# Main_4.net
KiCad netlist of a schematic drawn in Altium Designer
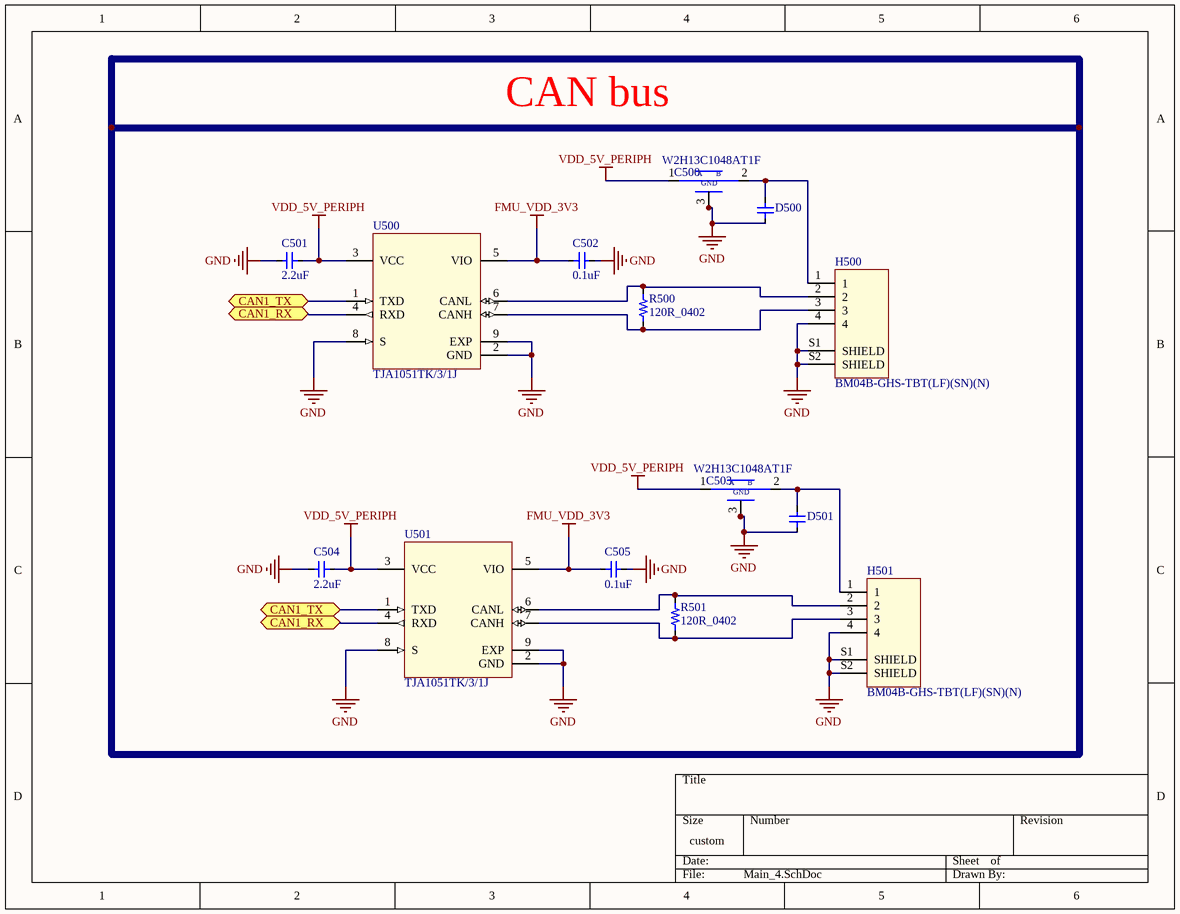
[diagram p0: Main_4.SchDoc]

(export (version "E")
  (design (tool "Eeschema 10.0.6"))
  (components
    (comp (ref "C500")
      (value "W2H13C1048AT1F")
      (footprint "W2H13C1048AT1F")
      (description "Feed Through Capacitors 25V 0.1uF X7R")
      (libsource (lib "UAV_mainboard") (part "W2H13C1048AT1F"))
    )
    (comp (ref "C501")
      (value "2.2uF")
      (footprint "C0603")
      (description "2.2 µF ±10% 10V Ceramic Capacitor X5R 0603 (1608 Metric)")
      (libsource (lib "UAV_mainboard") (part "CC0603KPX5R6BB225"))
    )
    (comp (ref "C502")
      (value "0.1uF")
      (footprint "C0603")
      (description "CAP CER 0.1UF 25V X7R 0603")
      (libsource (lib "UAV_mainboard") (part "CC0603KRX7R8BB104"))
    )
    (comp (ref "C503")
      (value "W2H13C1048AT1F")
      (footprint "W2H13C1048AT1F")
      (description "Feed Through Capacitors 25V 0.1uF X7R")
      (libsource (lib "UAV_mainboard") (part "W2H13C1048AT1F"))
    )
    (comp (ref "C504")
      (value "2.2uF")
      (footprint "C0603")
      (description "2.2 µF ±10% 10V Ceramic Capacitor X5R 0603 (1608 Metric)")
      (libsource (lib "UAV_mainboard") (part "CC0603KPX5R6BB225"))
    )
    (comp (ref "C505")
      (value "0.1uF")
      (footprint "C0603")
      (description "CAP CER 0.1UF 25V X7R 0603")
      (libsource (lib "UAV_mainboard") (part "CC0603KRX7R8BB104"))
    )
    (comp (ref "D500")
      (value "PESD0402-140")
      (footprint "PESD0402-140")
      (description "40V Clamp - Ipp Tvs Diode Surface Mount 0402")
      (libsource (lib "UAV_mainboard") (part "PESD0402-140"))
    )
    (comp (ref "D501")
      (value "PESD0402-140")
      (footprint "PESD0402-140")
      (description "40V Clamp - Ipp Tvs Diode Surface Mount 0402")
      (libsource (lib "UAV_mainboard") (part "PESD0402-140"))
    )
    (comp (ref "H500")
      (value "BM04B-GHS-TBT(LF)(SN)(N)")
      (footprint "BM04B-GHS-TBT(LF)(SN)(N)")
      (description "Connector Header Surface Mount 4 position 0.049\" (1.25mm)")
      (libsource (lib "UAV_mainboard") (part "BM04B-GHS-TBT(LF)(SN)(N)"))
    )
    (comp (ref "H501")
      (value "BM04B-GHS-TBT(LF)(SN)(N)")
      (footprint "BM04B-GHS-TBT(LF)(SN)(N)")
      (description "Connector Header Surface Mount 4 position 0.049\" (1.25mm)")
      (libsource (lib "UAV_mainboard") (part "BM04B-GHS-TBT(LF)(SN)(N)"))
    )
    (comp (ref "R500")
      (value "120R_0402")
      (footprint "R0402")
      (description "120 Ohms ±1% 0.063W, 1/16W Chip Resistor 0402 (1005 Metric) Moisture Resistant Thick Film")
      (libsource (lib "UAV_mainboard") (part "RC0402FR-07120RL"))
    )
    (comp (ref "R501")
      (value "120R_0402")
      (footprint "R0402")
      (description "120 Ohms ±1% 0.063W, 1/16W Chip Resistor 0402 (1005 Metric) Moisture Resistant Thick Film")
      (libsource (lib "UAV_mainboard") (part "RC0402FR-07120RL"))
    )
    (comp (ref "U500")
      (value "TJA1051TK/3/1J")
      (footprint "8HVSON")
      (description "IC TRANSCEIVER HALF 1/1 8HVSON")
      (libsource (lib "UAV_mainboard") (part "TJA1051TK/3/1J"))
    )
    (comp (ref "U501")
      (value "TJA1051TK/3/1J")
      (footprint "8HVSON")
      (description "IC TRANSCEIVER HALF 1/1 8HVSON")
      (libsource (lib "UAV_mainboard") (part "TJA1051TK/3/1J"))
    )
  )
  (nets
    (net (code "1") (name "/CAN1_RX") (class "Default")
      (node (ref "U500") (pin "4") (pinfunction "RXD_4") (pintype "output"))
      (node (ref "U501") (pin "4") (pinfunction "RXD_4") (pintype "output"))
    )
    (net (code "2") (name "/CAN1_TX") (class "Default")
      (node (ref "U500") (pin "1") (pinfunction "TXD_1") (pintype "input"))
      (node (ref "U501") (pin "1") (pinfunction "TXD_1") (pintype "input"))
    )
    (net (code "3") (name "FMU_VDD_3V3") (class "Default")
      (node (ref "C502") (pin "1") (pinfunction "1_1") (pintype "passive"))
      (node (ref "C505") (pin "1") (pinfunction "1_1") (pintype "passive"))
      (node (ref "U500") (pin "5") (pinfunction "VIO_5") (pintype "power_in"))
      (node (ref "U501") (pin "5") (pinfunction "VIO_5") (pintype "power_in"))
    )
    (net (code "4") (name "GND") (class "Default")
      (node (ref "C500") (pin "3") (pintype "passive"))
      (node (ref "C500") (pin "4") (pinfunction "4_4") (pintype "passive"))
      (node (ref "C501") (pin "2") (pinfunction "2_2") (pintype "passive"))
      (node (ref "C502") (pin "2") (pinfunction "2_2") (pintype "passive"))
      (node (ref "C503") (pin "3") (pintype "passive"))
      (node (ref "C503") (pin "4") (pinfunction "4_4") (pintype "passive"))
      (node (ref "C504") (pin "2") (pinfunction "2_2") (pintype "passive"))
      (node (ref "C505") (pin "2") (pinfunction "2_2") (pintype "passive"))
      (node (ref "D500") (pin "1") (pinfunction "1_1") (pintype "passive"))
      (node (ref "D501") (pin "1") (pinfunction "1_1") (pintype "passive"))
      (node (ref "H500") (pin "4") (pinfunction "4_4") (pintype "passive"))
      (node (ref "H500") (pin "S1") (pinfunction "SHIELD_S1") (pintype "passive"))
      (node (ref "H500") (pin "S2") (pinfunction "SHIELD_S2") (pintype "passive"))
      (node (ref "H501") (pin "4") (pinfunction "4_4") (pintype "passive"))
      (node (ref "H501") (pin "S1") (pinfunction "SHIELD_S1") (pintype "passive"))
      (node (ref "H501") (pin "S2") (pinfunction "SHIELD_S2") (pintype "passive"))
      (node (ref "U500") (pin "2") (pinfunction "GND_2") (pintype "power_in"))
      (node (ref "U500") (pin "8") (pinfunction "S_8") (pintype "input"))
      (node (ref "U500") (pin "9") (pinfunction "EXP_9") (pintype "power_in"))
      (node (ref "U501") (pin "2") (pinfunction "GND_2") (pintype "power_in"))
      (node (ref "U501") (pin "8") (pinfunction "S_8") (pintype "input"))
      (node (ref "U501") (pin "9") (pinfunction "EXP_9") (pintype "power_in"))
    )
    (net (code "5") (name "Net-(C500-Pad2)") (class "Default")
      (node (ref "C500") (pin "2") (pintype "passive"))
      (node (ref "D500") (pin "2") (pinfunction "2_2") (pintype "passive"))
      (node (ref "H500") (pin "1") (pinfunction "1_1") (pintype "passive"))
    )
    (net (code "6") (name "Net-(C503-Pad2)") (class "Default")
      (node (ref "C503") (pin "2") (pintype "passive"))
      (node (ref "D501") (pin "2") (pinfunction "2_2") (pintype "passive"))
      (node (ref "H501") (pin "1") (pinfunction "1_1") (pintype "passive"))
    )
    (net (code "7") (name "Net-(U500-CANH)") (class "Default")
      (node (ref "H500") (pin "3") (pinfunction "3_3") (pintype "passive"))
      (node (ref "R500") (pin "1") (pinfunction "1_1") (pintype "passive"))
      (node (ref "U500") (pin "7") (pinfunction "CANH_7") (pintype "bidirectional"))
    )
    (net (code "8") (name "Net-(U500-CANL)") (class "Default")
      (node (ref "H500") (pin "2") (pinfunction "2_2") (pintype "passive"))
      (node (ref "R500") (pin "2") (pinfunction "2_2") (pintype "passive"))
      (node (ref "U500") (pin "6") (pinfunction "CANL_6") (pintype "bidirectional"))
    )
    (net (code "9") (name "Net-(U501-CANH)") (class "Default")
      (node (ref "H501") (pin "3") (pinfunction "3_3") (pintype "passive"))
      (node (ref "R501") (pin "1") (pinfunction "1_1") (pintype "passive"))
      (node (ref "U501") (pin "7") (pinfunction "CANH_7") (pintype "bidirectional"))
    )
    (net (code "10") (name "Net-(U501-CANL)") (class "Default")
      (node (ref "H501") (pin "2") (pinfunction "2_2") (pintype "passive"))
      (node (ref "R501") (pin "2") (pinfunction "2_2") (pintype "passive"))
      (node (ref "U501") (pin "6") (pinfunction "CANL_6") (pintype "bidirectional"))
    )
    (net (code "11") (name "VDD_5V_PERIPH") (class "Default")
      (node (ref "C500") (pin "1") (pintype "passive"))
      (node (ref "C501") (pin "1") (pinfunction "1_1") (pintype "passive"))
      (node (ref "C503") (pin "1") (pintype "passive"))
      (node (ref "C504") (pin "1") (pinfunction "1_1") (pintype "passive"))
      (node (ref "U500") (pin "3") (pinfunction "VCC_3") (pintype "power_in"))
      (node (ref "U501") (pin "3") (pinfunction "VCC_3") (pintype "power_in"))
    )
  )
)
